# USB-UART.net
KiCad netlist of a schematic drawn in Altium Designer
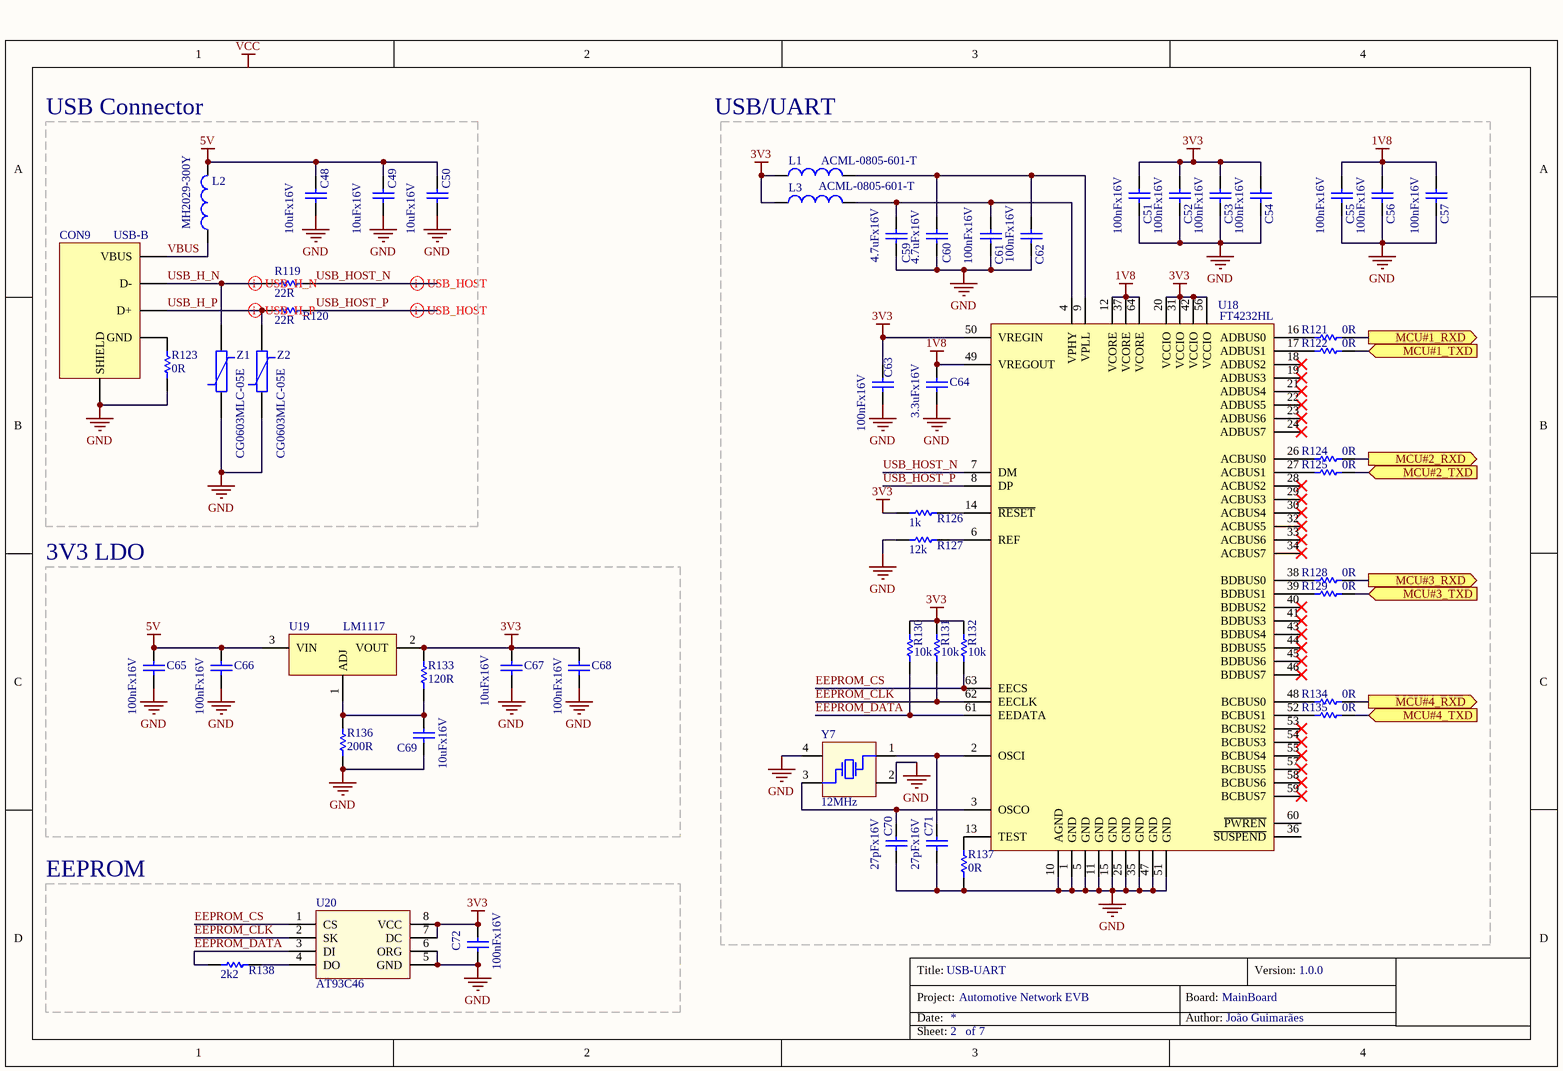
[diagram p0: USB-UART.SchDoc]

(export (version "E")
  (design (tool "Eeschema 10.0.6"))
  (components
    (comp (ref "C48")
      (value "10uFx16V")
      (footprint "DISC-0805")
      (description "Capacitor")
      (libsource (lib "IntLib") (part "Cap"))
    )
    (comp (ref "C49")
      (value "10uFx16V")
      (footprint "DISC-0805")
      (description "Capacitor")
      (libsource (lib "IntLib") (part "Cap"))
    )
    (comp (ref "C50")
      (value "10uFx16V")
      (footprint "DISC-0805")
      (description "Capacitor")
      (libsource (lib "IntLib") (part "Cap"))
    )
    (comp (ref "C51")
      (value "100nFx16V")
      (footprint "DISC-0603")
      (description "Capacitor")
      (libsource (lib "IntLib") (part "Cap"))
    )
    (comp (ref "C52")
      (value "100nFx16V")
      (footprint "DISC-0603")
      (description "Capacitor")
      (libsource (lib "IntLib") (part "Cap"))
    )
    (comp (ref "C53")
      (value "100nFx16V")
      (footprint "DISC-0603")
      (description "Capacitor")
      (libsource (lib "IntLib") (part "Cap"))
    )
    (comp (ref "C54")
      (value "100nFx16V")
      (footprint "DISC-0603")
      (description "Capacitor")
      (libsource (lib "IntLib") (part "Cap"))
    )
    (comp (ref "C55")
      (value "100nFx16V")
      (footprint "DISC-0603")
      (description "Capacitor")
      (libsource (lib "IntLib") (part "Cap"))
    )
    (comp (ref "C56")
      (value "100nFx16V")
      (footprint "DISC-0603")
      (description "Capacitor")
      (libsource (lib "IntLib") (part "Cap"))
    )
    (comp (ref "C57")
      (value "100nFx16V")
      (footprint "DISC-0603")
      (description "Capacitor")
      (libsource (lib "IntLib") (part "Cap"))
    )
    (comp (ref "C59")
      (value "4.7uFx16V")
      (footprint "DISC-0805")
      (description "Capacitor")
      (libsource (lib "IntLib") (part "Cap"))
    )
    (comp (ref "C60")
      (value "4.7uFx16V")
      (footprint "DISC-0805")
      (description "Capacitor")
      (libsource (lib "IntLib") (part "Cap"))
    )
    (comp (ref "C61")
      (value "100nFx16V")
      (footprint "DISC-0603")
      (description "Capacitor")
      (libsource (lib "IntLib") (part "Cap"))
    )
    (comp (ref "C62")
      (value "100nFx16V")
      (footprint "DISC-0603")
      (description "Capacitor")
      (libsource (lib "IntLib") (part "Cap"))
    )
    (comp (ref "C63")
      (value "100nFx16V")
      (footprint "DISC-0603")
      (description "Capacitor")
      (libsource (lib "IntLib") (part "Cap"))
    )
    (comp (ref "C64")
      (value "3.3uFx16V")
      (footprint "DISC-0603")
      (description "Capacitor")
      (libsource (lib "IntLib") (part "Cap"))
    )
    (comp (ref "C65")
      (value "100nFx16V")
      (footprint "DISC-0603")
      (description "Capacitor")
      (libsource (lib "IntLib") (part "Cap"))
    )
    (comp (ref "C66")
      (value "100nFx16V")
      (footprint "DISC-0603")
      (description "Capacitor")
      (libsource (lib "IntLib") (part "Cap"))
    )
    (comp (ref "C67")
      (value "10uFx16V")
      (footprint "DISC-0805")
      (description "Capacitor")
      (libsource (lib "IntLib") (part "Cap"))
    )
    (comp (ref "C68")
      (value "100nFx16V")
      (footprint "DISC-0603")
      (description "Capacitor")
      (libsource (lib "IntLib") (part "Cap"))
    )
    (comp (ref "C69")
      (value "10uFx16V")
      (footprint "DISC-0805")
      (description "Capacitor")
      (libsource (lib "IntLib") (part "Cap"))
    )
    (comp (ref "C70")
      (value "27pFx16V")
      (footprint "DISC-0603")
      (description "Capacitor")
      (libsource (lib "IntLib") (part "Cap"))
    )
    (comp (ref "C71")
      (value "27pFx16V")
      (footprint "DISC-0603")
      (description "Capacitor")
      (libsource (lib "IntLib") (part "Cap"))
    )
    (comp (ref "C72")
      (value "100nFx16V")
      (footprint "DISC-0603")
      (description "Capacitor")
      (libsource (lib "IntLib") (part "Cap"))
    )
    (comp (ref "CON9")
      (value "USB-B")
      (footprint "CON-USB-B")
      (description "USB Type-B")
      (libsource (lib "IntLib") (part "USB Type-B"))
    )
    (comp (ref "L1")
      (value "ACML-0805-601-T")
      (footprint "DISC-0805")
      (description "Chip Inductor")
      (libsource (lib "IntLib") (part "Inductor"))
    )
    (comp (ref "L2")
      (value "MH2029-300Y")
      (footprint "DISC-0805")
      (description "Chip Inductor")
      (libsource (lib "IntLib") (part "Inductor"))
    )
    (comp (ref "L3")
      (value "ACML-0805-601-T")
      (footprint "DISC-0805")
      (description "Chip Inductor")
      (libsource (lib "IntLib") (part "Inductor"))
    )
    (comp (ref "R119")
      (value "22R")
      (footprint "DISC-0603")
      (description "Resistor")
      (libsource (lib "IntLib") (part "Res"))
    )
    (comp (ref "R120")
      (value "22R")
      (footprint "DISC-0603")
      (description "Resistor")
      (libsource (lib "IntLib") (part "Res"))
    )
    (comp (ref "R121")
      (value "0R")
      (footprint "DISC-0603")
      (description "Resistor")
      (libsource (lib "IntLib") (part "Res"))
    )
    (comp (ref "R122")
      (value "0R")
      (footprint "DISC-0603")
      (description "Resistor")
      (libsource (lib "IntLib") (part "Res"))
    )
    (comp (ref "R123")
      (value "0R")
      (footprint "DISC-0603")
      (description "Resistor")
      (libsource (lib "IntLib") (part "Res"))
    )
    (comp (ref "R124")
      (value "0R")
      (footprint "DISC-0603")
      (description "Resistor")
      (libsource (lib "IntLib") (part "Res"))
    )
    (comp (ref "R125")
      (value "0R")
      (footprint "DISC-0603")
      (description "Resistor")
      (libsource (lib "IntLib") (part "Res"))
    )
    (comp (ref "R126")
      (value "1k")
      (footprint "DISC-0603")
      (description "Resistor")
      (libsource (lib "IntLib") (part "Res"))
    )
    (comp (ref "R127")
      (value "12k")
      (footprint "DISC-0603")
      (description "Resistor")
      (libsource (lib "IntLib") (part "Res"))
    )
    (comp (ref "R128")
      (value "0R")
      (footprint "DISC-0603")
      (description "Resistor")
      (libsource (lib "IntLib") (part "Res"))
    )
    (comp (ref "R129")
      (value "0R")
      (footprint "DISC-0603")
      (description "Resistor")
      (libsource (lib "IntLib") (part "Res"))
    )
    (comp (ref "R130")
      (value "10k")
      (footprint "DISC-0603")
      (description "Resistor")
      (libsource (lib "IntLib") (part "Res"))
    )
    (comp (ref "R131")
      (value "10k")
      (footprint "DISC-0603")
      (description "Resistor")
      (libsource (lib "IntLib") (part "Res"))
    )
    (comp (ref "R132")
      (value "10k")
      (footprint "DISC-0603")
      (description "Resistor")
      (libsource (lib "IntLib") (part "Res"))
    )
    (comp (ref "R133")
      (value "120R")
      (footprint "DISC-0603")
      (description "Resistor")
      (libsource (lib "IntLib") (part "Res"))
    )
    (comp (ref "R134")
      (value "0R")
      (footprint "DISC-0603")
      (description "Resistor")
      (libsource (lib "IntLib") (part "Res"))
    )
    (comp (ref "R135")
      (value "0R")
      (footprint "DISC-0603")
      (description "Resistor")
      (libsource (lib "IntLib") (part "Res"))
    )
    (comp (ref "R136")
      (value "200R")
      (footprint "DISC-0603")
      (description "Resistor")
      (libsource (lib "IntLib") (part "Res"))
    )
    (comp (ref "R137")
      (value "0R")
      (footprint "DISC-0603")
      (description "Resistor")
      (libsource (lib "IntLib") (part "Res"))
    )
    (comp (ref "R138")
      (value "2k2")
      (footprint "DISC-0603")
      (description "Resistor")
      (libsource (lib "IntLib") (part "Res"))
    )
    (comp (ref "U18")
      (value "FT4232HL")
      (footprint "CI-LQFP-64")
      (description "Quad High Speed USB to Multipurpose UART/MPSSE")
      (libsource (lib "IntLib") (part "FT4232HL"))
    )
    (comp (ref "U19")
      (value "LM1117")
      (footprint "DISC-SOT-223")
      (description "Wide Temperature Three-Pin Adjustable Regulator")
      (libsource (lib "IntLib") (part "LM317-N"))
    )
    (comp (ref "U20")
      (value "AT93C46")
      (footprint "CI-SOIC-8")
      (description "3-wire Serial EEPROMs")
      (libsource (lib "IntLib") (part "AT93C46"))
    )
    (comp (ref "Y7")
      (value "12MHz")
      (footprint "DISC-CRYSTAL-4P-7X5")
      (description "ABMM-12.000MHZ-B2-T")
      (libsource (lib "IntLib") (part "XTAL-4-PIN"))
    )
    (comp (ref "Z1")
      (value "CG0603MLC-05E")
      (footprint "DISC-0603")
      (description "Varistor")
      (libsource (lib "IntLib") (part "Varistor"))
    )
    (comp (ref "Z2")
      (value "CG0603MLC-05E")
      (footprint "DISC-0603")
      (description "Varistor")
      (libsource (lib "IntLib") (part "Varistor"))
    )
  )
  (nets
    (net (code "1") (name "/EEPROM_CLK") (class "Default")
      (node (ref "R131") (pin "1") (pinfunction "1_1") (pintype "passive"))
      (node (ref "U18") (pin "62") (pinfunction "EECLK_62") (pintype "passive"))
      (node (ref "U20") (pin "2") (pinfunction "SK_2") (pintype "passive"))
    )
    (net (code "2") (name "/EEPROM_CS") (class "Default")
      (node (ref "R132") (pin "1") (pinfunction "1_1") (pintype "passive"))
      (node (ref "U18") (pin "63") (pinfunction "EECS_63") (pintype "passive"))
      (node (ref "U20") (pin "1") (pinfunction "CS_1") (pintype "passive"))
    )
    (net (code "3") (name "/EEPROM_DATA") (class "Default")
      (node (ref "R130") (pin "1") (pinfunction "1_1") (pintype "passive"))
      (node (ref "R138") (pin "1") (pinfunction "1_1") (pintype "passive"))
      (node (ref "U18") (pin "61") (pinfunction "EEDATA_61") (pintype "passive"))
      (node (ref "U20") (pin "3") (pinfunction "DI_3") (pintype "passive"))
    )
    (net (code "4") (name "/MCU#1_RXD") (class "Default")
      (node (ref "R121") (pin "2") (pinfunction "2_2") (pintype "passive"))
    )
    (net (code "5") (name "/MCU#1_TXD") (class "Default")
      (node (ref "R122") (pin "2") (pinfunction "2_2") (pintype "passive"))
    )
    (net (code "6") (name "/MCU#2_RXD") (class "Default")
      (node (ref "R124") (pin "2") (pinfunction "2_2") (pintype "passive"))
    )
    (net (code "7") (name "/MCU#2_TXD") (class "Default")
      (node (ref "R125") (pin "2") (pinfunction "2_2") (pintype "passive"))
    )
    (net (code "8") (name "/MCU#3_RXD") (class "Default")
      (node (ref "R128") (pin "2") (pinfunction "2_2") (pintype "passive"))
    )
    (net (code "9") (name "/MCU#3_TXD") (class "Default")
      (node (ref "R129") (pin "2") (pinfunction "2_2") (pintype "passive"))
    )
    (net (code "10") (name "/MCU#4_RXD") (class "Default")
      (node (ref "R134") (pin "2") (pinfunction "2_2") (pintype "passive"))
    )
    (net (code "11") (name "/MCU#4_TXD") (class "Default")
      (node (ref "R135") (pin "2") (pinfunction "2_2") (pintype "passive"))
    )
    (net (code "12") (name "/USB_HOST_N") (class "Default")
      (node (ref "R119") (pin "2") (pinfunction "2_2") (pintype "passive"))
      (node (ref "U18") (pin "7") (pinfunction "DM_7") (pintype "passive"))
    )
    (net (code "13") (name "/USB_HOST_P") (class "Default")
      (node (ref "R120") (pin "2") (pinfunction "2_2") (pintype "passive"))
      (node (ref "U18") (pin "8") (pinfunction "DP_8") (pintype "passive"))
    )
    (net (code "14") (name "/USB_H_N") (class "Default")
      (node (ref "CON9") (pin "2") (pinfunction "D-_2") (pintype "passive"))
      (node (ref "R119") (pin "1") (pinfunction "1_1") (pintype "passive"))
      (node (ref "Z1") (pin "2") (pinfunction "2_2") (pintype "passive"))
    )
    (net (code "15") (name "/USB_H_P") (class "Default")
      (node (ref "CON9") (pin "3") (pinfunction "D+_3") (pintype "passive"))
      (node (ref "R120") (pin "1") (pinfunction "1_1") (pintype "passive"))
      (node (ref "Z2") (pin "2") (pinfunction "2_2") (pintype "passive"))
    )
    (net (code "16") (name "/VBUS") (class "Default")
      (node (ref "CON9") (pin "1") (pinfunction "VBUS_1") (pintype "passive"))
      (node (ref "L2") (pin "1") (pinfunction "1_1") (pintype "passive"))
    )
    (net (code "17") (name "1V8") (class "Default")
      (node (ref "C55") (pin "1") (pinfunction "1_1") (pintype "passive"))
      (node (ref "C56") (pin "1") (pinfunction "1_1") (pintype "passive"))
      (node (ref "C57") (pin "1") (pinfunction "1_1") (pintype "passive"))
      (node (ref "C64") (pin "1") (pinfunction "1_1") (pintype "passive"))
      (node (ref "U18") (pin "12") (pinfunction "VCORE_12") (pintype "passive"))
      (node (ref "U18") (pin "37") (pinfunction "VCORE_37") (pintype "passive"))
      (node (ref "U18") (pin "49") (pinfunction "VREGOUT_49") (pintype "passive"))
      (node (ref "U18") (pin "64") (pinfunction "VCORE_64") (pintype "passive"))
    )
    (net (code "18") (name "3V3") (class "Default")
      (node (ref "C51") (pin "1") (pinfunction "1_1") (pintype "passive"))
      (node (ref "C52") (pin "1") (pinfunction "1_1") (pintype "passive"))
      (node (ref "C53") (pin "1") (pinfunction "1_1") (pintype "passive"))
      (node (ref "C54") (pin "1") (pinfunction "1_1") (pintype "passive"))
      (node (ref "C63") (pin "1") (pinfunction "1_1") (pintype "passive"))
      (node (ref "C67") (pin "1") (pinfunction "1_1") (pintype "passive"))
      (node (ref "C68") (pin "1") (pinfunction "1_1") (pintype "passive"))
      (node (ref "C72") (pin "1") (pinfunction "1_1") (pintype "passive"))
      (node (ref "L1") (pin "1") (pinfunction "1_1") (pintype "passive"))
      (node (ref "L3") (pin "1") (pinfunction "1_1") (pintype "passive"))
      (node (ref "R126") (pin "1") (pinfunction "1_1") (pintype "passive"))
      (node (ref "R130") (pin "2") (pinfunction "2_2") (pintype "passive"))
      (node (ref "R131") (pin "2") (pinfunction "2_2") (pintype "passive"))
      (node (ref "R132") (pin "2") (pinfunction "2_2") (pintype "passive"))
      (node (ref "R133") (pin "2") (pinfunction "2_2") (pintype "passive"))
      (node (ref "U18") (pin "20") (pinfunction "VCCIO_20") (pintype "passive"))
      (node (ref "U18") (pin "31") (pinfunction "VCCIO_31") (pintype "passive"))
      (node (ref "U18") (pin "42") (pinfunction "VCCIO_42") (pintype "passive"))
      (node (ref "U18") (pin "50") (pinfunction "VREGIN_50") (pintype "passive"))
      (node (ref "U18") (pin "56") (pinfunction "VCCIO_56") (pintype "passive"))
      (node (ref "U19") (pin "2") (pinfunction "VOUT_2") (pintype "passive"))
      (node (ref "U19") (pin "4") (pinfunction "VOUT_4") (pintype "passive"))
      (node (ref "U20") (pin "7") (pinfunction "DC_7") (pintype "passive"))
      (node (ref "U20") (pin "8") (pinfunction "VCC_8") (pintype "passive"))
    )
    (net (code "19") (name "5V") (class "Default")
      (node (ref "C48") (pin "1") (pinfunction "1_1") (pintype "passive"))
      (node (ref "C49") (pin "1") (pinfunction "1_1") (pintype "passive"))
      (node (ref "C50") (pin "1") (pinfunction "1_1") (pintype "passive"))
      (node (ref "C65") (pin "1") (pinfunction "1_1") (pintype "passive"))
      (node (ref "C66") (pin "1") (pinfunction "1_1") (pintype "passive"))
      (node (ref "L2") (pin "2") (pinfunction "2_2") (pintype "passive"))
      (node (ref "U19") (pin "3") (pinfunction "VIN_3") (pintype "power_in"))
    )
    (net (code "20") (name "GND") (class "Default")
      (node (ref "C48") (pin "2") (pinfunction "2_2") (pintype "passive"))
      (node (ref "C49") (pin "2") (pinfunction "2_2") (pintype "passive"))
      (node (ref "C50") (pin "2") (pinfunction "2_2") (pintype "passive"))
      (node (ref "C51") (pin "2") (pinfunction "2_2") (pintype "passive"))
      (node (ref "C52") (pin "2") (pinfunction "2_2") (pintype "passive"))
      (node (ref "C53") (pin "2") (pinfunction "2_2") (pintype "passive"))
      (node (ref "C54") (pin "2") (pinfunction "2_2") (pintype "passive"))
      (node (ref "C55") (pin "2") (pinfunction "2_2") (pintype "passive"))
      (node (ref "C56") (pin "2") (pinfunction "2_2") (pintype "passive"))
      (node (ref "C57") (pin "2") (pinfunction "2_2") (pintype "passive"))
      (node (ref "C59") (pin "2") (pinfunction "2_2") (pintype "passive"))
      (node (ref "C60") (pin "2") (pinfunction "2_2") (pintype "passive"))
      (node (ref "C61") (pin "2") (pinfunction "2_2") (pintype "passive"))
      (node (ref "C62") (pin "2") (pinfunction "2_2") (pintype "passive"))
      (node (ref "C63") (pin "2") (pinfunction "2_2") (pintype "passive"))
      (node (ref "C64") (pin "2") (pinfunction "2_2") (pintype "passive"))
      (node (ref "C65") (pin "2") (pinfunction "2_2") (pintype "passive"))
      (node (ref "C66") (pin "2") (pinfunction "2_2") (pintype "passive"))
      (node (ref "C67") (pin "2") (pinfunction "2_2") (pintype "passive"))
      (node (ref "C68") (pin "2") (pinfunction "2_2") (pintype "passive"))
      (node (ref "C69") (pin "2") (pinfunction "2_2") (pintype "passive"))
      (node (ref "C70") (pin "1") (pinfunction "1_1") (pintype "passive"))
      (node (ref "C71") (pin "1") (pinfunction "1_1") (pintype "passive"))
      (node (ref "C72") (pin "2") (pinfunction "2_2") (pintype "passive"))
      (node (ref "CON9") (pin "5") (pinfunction "SHIELD_5") (pintype "passive"))
      (node (ref "CON9") (pin "6") (pinfunction "SHIELD_6") (pintype "passive"))
      (node (ref "R123") (pin "1") (pinfunction "1_1") (pintype "passive"))
      (node (ref "R127") (pin "1") (pinfunction "1_1") (pintype "passive"))
      (node (ref "R136") (pin "1") (pinfunction "1_1") (pintype "passive"))
      (node (ref "R137") (pin "1") (pinfunction "1_1") (pintype "passive"))
      (node (ref "U18") (pin "1") (pinfunction "GND_1") (pintype "passive"))
      (node (ref "U18") (pin "10") (pinfunction "AGND_10") (pintype "passive"))
      (node (ref "U18") (pin "11") (pinfunction "GND_11") (pintype "passive"))
      (node (ref "U18") (pin "15") (pinfunction "GND_15") (pintype "passive"))
      (node (ref "U18") (pin "25") (pinfunction "GND_25") (pintype "passive"))
      (node (ref "U18") (pin "35") (pinfunction "GND_35") (pintype "passive"))
      (node (ref "U18") (pin "47") (pinfunction "GND_47") (pintype "passive"))
      (node (ref "U18") (pin "5") (pinfunction "GND_5") (pintype "passive"))
      (node (ref "U18") (pin "51") (pinfunction "GND_51") (pintype "passive"))
      (node (ref "U20") (pin "5") (pinfunction "GND_5") (pintype "passive"))
      (node (ref "U20") (pin "6") (pinfunction "ORG_6") (pintype "passive"))
      (node (ref "Y7") (pin "2") (pinfunction "GND_2") (pintype "passive"))
      (node (ref "Y7") (pin "4") (pinfunction "GND_4") (pintype "passive"))
      (node (ref "Z1") (pin "1") (pinfunction "1_1") (pintype "passive"))
      (node (ref "Z2") (pin "1") (pinfunction "1_1") (pintype "passive"))
    )
    (net (code "21") (name "Net-(CON9-GND)") (class "Default")
      (node (ref "CON9") (pin "4") (pinfunction "GND_4") (pintype "passive"))
      (node (ref "R123") (pin "2") (pinfunction "2_2") (pintype "passive"))
    )
    (net (code "22") (name "Net-(U18-ACBUS0)") (class "Default")
      (node (ref "R124") (pin "1") (pinfunction "1_1") (pintype "passive"))
      (node (ref "U18") (pin "26") (pinfunction "ACBUS0_26") (pintype "passive"))
    )
    (net (code "23") (name "Net-(U18-ACBUS1)") (class "Default")
      (node (ref "R125") (pin "1") (pinfunction "1_1") (pintype "passive"))
      (node (ref "U18") (pin "27") (pinfunction "ACBUS1_27") (pintype "passive"))
    )
    (net (code "24") (name "Net-(U18-ADBUS0)") (class "Default")
      (node (ref "R121") (pin "1") (pinfunction "1_1") (pintype "passive"))
      (node (ref "U18") (pin "16") (pinfunction "ADBUS0_16") (pintype "passive"))
    )
    (net (code "25") (name "Net-(U18-ADBUS1)") (class "Default")
      (node (ref "R122") (pin "1") (pinfunction "1_1") (pintype "passive"))
      (node (ref "U18") (pin "17") (pinfunction "ADBUS1_17") (pintype "passive"))
    )
    (net (code "26") (name "Net-(U18-BCBUS0)") (class "Default")
      (node (ref "R134") (pin "1") (pinfunction "1_1") (pintype "passive"))
      (node (ref "U18") (pin "48") (pinfunction "BCBUS0_48") (pintype "passive"))
    )
    (net (code "27") (name "Net-(U18-BCBUS1)") (class "Default")
      (node (ref "R135") (pin "1") (pinfunction "1_1") (pintype "passive"))
      (node (ref "U18") (pin "52") (pinfunction "BCBUS1_52") (pintype "passive"))
    )
    (net (code "28") (name "Net-(U18-BDBUS0)") (class "Default")
      (node (ref "R128") (pin "1") (pinfunction "1_1") (pintype "passive"))
      (node (ref "U18") (pin "38") (pinfunction "BDBUS0_38") (pintype "passive"))
    )
    (net (code "29") (name "Net-(U18-BDBUS1)") (class "Default")
      (node (ref "R129") (pin "1") (pinfunction "1_1") (pintype "passive"))
      (node (ref "U18") (pin "39") (pinfunction "BDBUS1_39") (pintype "passive"))
    )
    (net (code "30") (name "Net-(U18-OSCI)") (class "Default")
      (node (ref "C71") (pin "2") (pinfunction "2_2") (pintype "passive"))
      (node (ref "U18") (pin "2") (pinfunction "OSCI_2") (pintype "passive"))
      (node (ref "Y7") (pin "1") (pinfunction "OSC1_1") (pintype "passive"))
    )
    (net (code "31") (name "Net-(U18-OSCO)") (class "Default")
      (node (ref "C70") (pin "2") (pinfunction "2_2") (pintype "passive"))
      (node (ref "U18") (pin "3") (pinfunction "OSCO_3") (pintype "passive"))
      (node (ref "Y7") (pin "3") (pinfunction "OSC2_3") (pintype "passive"))
    )
    (net (code "32") (name "Net-(U18-REF)") (class "Default")
      (node (ref "R127") (pin "2") (pinfunction "2_2") (pintype "passive"))
      (node (ref "U18") (pin "6") (pinfunction "REF_6") (pintype "passive"))
    )
    (net (code "33") (name "Net-(U18-TEST)") (class "Default")
      (node (ref "R137") (pin "2") (pinfunction "2_2") (pintype "passive"))
      (node (ref "U18") (pin "13") (pinfunction "TEST_13") (pintype "passive"))
    )
    (net (code "34") (name "Net-(U18-VPHY)") (class "Default")
      (node (ref "C59") (pin "1") (pinfunction "1_1") (pintype "passive"))
      (node (ref "C61") (pin "1") (pinfunction "1_1") (pintype "passive"))
      (node (ref "L3") (pin "2") (pinfunction "2_2") (pintype "passive"))
      (node (ref "U18") (pin "4") (pinfunction "VPHY_4") (pintype "passive"))
    )
    (net (code "35") (name "Net-(U18-VPLL)") (class "Default")
      (node (ref "C60") (pin "1") (pinfunction "1_1") (pintype "passive"))
      (node (ref "C62") (pin "1") (pinfunction "1_1") (pintype "passive"))
      (node (ref "L1") (pin "2") (pinfunction "2_2") (pintype "passive"))
      (node (ref "U18") (pin "9") (pinfunction "VPLL_9") (pintype "passive"))
    )
    (net (code "36") (name "Net-(U18-~{RESET})") (class "Default")
      (node (ref "R126") (pin "2") (pinfunction "2_2") (pintype "passive"))
      (node (ref "U18") (pin "14") (pinfunction "~{RESET}_14") (pintype "passive"))
    )
    (net (code "37") (name "Net-(U19-ADJ)") (class "Default")
      (node (ref "C69") (pin "1") (pinfunction "1_1") (pintype "passive"))
      (node (ref "R133") (pin "1") (pinfunction "1_1") (pintype "passive"))
      (node (ref "R136") (pin "2") (pinfunction "2_2") (pintype "passive"))
      (node (ref "U19") (pin "1") (pinfunction "ADJ_1") (pintype "power_in"))
    )
    (net (code "38") (name "Net-(U20-DO)") (class "Default")
      (node (ref "R138") (pin "2") (pinfunction "2_2") (pintype "passive"))
      (node (ref "U20") (pin "4") (pinfunction "DO_4") (pintype "passive"))
    )
    (net (code "40") (name "unconnected-(U18-ACBUS2-Pad28)") (class "Default")
      (node (ref "U18") (pin "28") (pinfunction "ACBUS2_28") (pintype "passive+no_connect"))
    )
    (net (code "41") (name "unconnected-(U18-ACBUS3-Pad29)") (class "Default")
      (node (ref "U18") (pin "29") (pinfunction "ACBUS3_29") (pintype "passive+no_connect"))
    )
    (net (code "42") (name "unconnected-(U18-ACBUS4-Pad30)") (class "Default")
      (node (ref "U18") (pin "30") (pinfunction "ACBUS4_30") (pintype "passive+no_connect"))
    )
    (net (code "43") (name "unconnected-(U18-ACBUS5-Pad32)") (class "Default")
      (node (ref "U18") (pin "32") (pinfunction "ACBUS5_32") (pintype "passive+no_connect"))
    )
    (net (code "44") (name "unconnected-(U18-ACBUS6-Pad33)") (class "Default")
      (node (ref "U18") (pin "33") (pinfunction "ACBUS6_33") (pintype "passive+no_connect"))
    )
    (net (code "45") (name "unconnected-(U18-ACBUS7-Pad34)") (class "Default")
      (node (ref "U18") (pin "34") (pinfunction "ACBUS7_34") (pintype "passive+no_connect"))
    )
    (net (code "46") (name "unconnected-(U18-ADBUS2-Pad18)") (class "Default")
      (node (ref "U18") (pin "18") (pinfunction "ADBUS2_18") (pintype "passive+no_connect"))
    )
    (net (code "47") (name "unconnected-(U18-ADBUS3-Pad19)") (class "Default")
      (node (ref "U18") (pin "19") (pinfunction "ADBUS3_19") (pintype "passive+no_connect"))
    )
    (net (code "48") (name "unconnected-(U18-ADBUS4-Pad21)") (class "Default")
      (node (ref "U18") (pin "21") (pinfunction "ADBUS4_21") (pintype "passive+no_connect"))
    )
    (net (code "49") (name "unconnected-(U18-ADBUS5-Pad22)") (class "Default")
      (node (ref "U18") (pin "22") (pinfunction "ADBUS5_22") (pintype "passive+no_connect"))
    )
    (net (code "50") (name "unconnected-(U18-ADBUS6-Pad23)") (class "Default")
      (node (ref "U18") (pin "23") (pinfunction "ADBUS6_23") (pintype "passive+no_connect"))
    )
    (net (code "51") (name "unconnected-(U18-ADBUS7-Pad24)") (class "Default")
      (node (ref "U18") (pin "24") (pinfunction "ADBUS7_24") (pintype "passive+no_connect"))
    )
    (net (code "52") (name "unconnected-(U18-BCBUS2-Pad53)") (class "Default")
      (node (ref "U18") (pin "53") (pinfunction "BCBUS2_53") (pintype "passive+no_connect"))
    )
    (net (code "53") (name "unconnected-(U18-BCBUS3-Pad54)") (class "Default")
      (node (ref "U18") (pin "54") (pinfunction "BCBUS3_54") (pintype "passive+no_connect"))
    )
    (net (code "54") (name "unconnected-(U18-BCBUS4-Pad55)") (class "Default")
      (node (ref "U18") (pin "55") (pinfunction "BCBUS4_55") (pintype "passive+no_connect"))
    )
    (net (code "55") (name "unconnected-(U18-BCBUS5-Pad57)") (class "Default")
      (node (ref "U18") (pin "57") (pinfunction "BCBUS5_57") (pintype "passive+no_connect"))
    )
    (net (code "56") (name "unconnected-(U18-BCBUS6-Pad58)") (class "Default")
      (node (ref "U18") (pin "58") (pinfunction "BCBUS6_58") (pintype "passive+no_connect"))
    )
    (net (code "57") (name "unconnected-(U18-BCBUS7-Pad59)") (class "Default")
      (node (ref "U18") (pin "59") (pinfunction "BCBUS7_59") (pintype "passive+no_connect"))
    )
    (net (code "58") (name "unconnected-(U18-BDBUS2-Pad40)") (class "Default")
      (node (ref "U18") (pin "40") (pinfunction "BDBUS2_40") (pintype "passive+no_connect"))
    )
    (net (code "59") (name "unconnected-(U18-BDBUS3-Pad41)") (class "Default")
      (node (ref "U18") (pin "41") (pinfunction "BDBUS3_41") (pintype "passive+no_connect"))
    )
    (net (code "60") (name "unconnected-(U18-BDBUS4-Pad43)") (class "Default")
      (node (ref "U18") (pin "43") (pinfunction "BDBUS4_43") (pintype "passive+no_connect"))
    )
    (net (code "61") (name "unconnected-(U18-BDBUS5-Pad44)") (class "Default")
      (node (ref "U18") (pin "44") (pinfunction "BDBUS5_44") (pintype "passive+no_connect"))
    )
    (net (code "62") (name "unconnected-(U18-BDBUS6-Pad45)") (class "Default")
      (node (ref "U18") (pin "45") (pinfunction "BDBUS6_45") (pintype "passive+no_connect"))
    )
    (net (code "63") (name "unconnected-(U18-BDBUS7-Pad46)") (class "Default")
      (node (ref "U18") (pin "46") (pinfunction "BDBUS7_46") (pintype "passive+no_connect"))
    )
    (net (code "64") (name "unconnected-(U18-~{PWREN}-Pad60)") (class "Default")
      (node (ref "U18") (pin "60") (pinfunction "~{PWREN}_60") (pintype "passive"))
    )
    (net (code "65") (name "unconnected-(U18-~{SUSPEND}-Pad36)") (class "Default")
      (node (ref "U18") (pin "36") (pinfunction "~{SUSPEND}_36") (pintype "passive"))
    )
  )
)
